# Power.net
KiCad netlist of a schematic drawn in Altium Designer
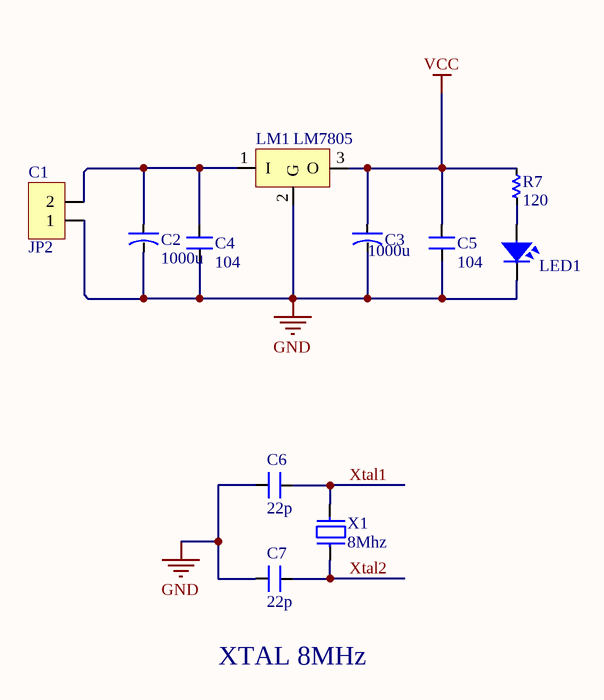
[diagram p0: Power.SchDoc]

(export (version "E")
  (design (tool "Eeschema 10.0.6"))
  (components
    (comp (ref "C1")
      (value "JP2")
      (footprint "JP2-D1T")
      (description "WR-PHD 2.54 mm Angled Socket Header")
      (fields
        (field (name "MANUFACTURER") "Würth Elektronik eiSos GmbH")
        (field (name "PARTNO") "613002143121")
        (field (name "CREATED BY") "Karrer Zheng")
      )
      (libsource (lib "LIBRARY") (part "JP2"))
    )
    (comp (ref "C2")
      (value "1000u")
      (footprint "CA-ALU-2.54")
      (description "Capacitor (Semiconductor SIM Model)")
      (fields (field (name "PUBLISHER") "Altium Limited"))
      (libsource (lib "LIBRARY") (part "CN-ALU-DIP"))
    )
    (comp (ref "C3")
      (value "1000u")
      (footprint "CA-ALU-2.54")
      (description "Capacitor (Semiconductor SIM Model)")
      (fields (field (name "PUBLISHER") "Altium Limited"))
      (libsource (lib "LIBRARY") (part "CN-ALU-DIP"))
    )
    (comp (ref "C4")
      (value "104")
      (footprint "C-SE-7,5x11x13x9x4")
      (description "Capacitor (Semiconductor SIM Model)")
      (fields (field (name "PUBLISHER") "Altium Limited"))
      (libsource (lib "LIBRARY") (part "CN-SEMI-DIP"))
    )
    (comp (ref "C5")
      (value "104")
      (footprint "C-SE-7,5x11x13x9x4")
      (description "Capacitor (Semiconductor SIM Model)")
      (fields (field (name "PUBLISHER") "Altium Limited"))
      (libsource (lib "LIBRARY") (part "CN-SEMI-DIP"))
    )
    (comp (ref "C6")
      (value "22p")
      (footprint "C-SE-7,5x11x13x9x4")
      (description "Capacitor (Semiconductor SIM Model)")
      (fields (field (name "PUBLISHER") "Altium Limited"))
      (libsource (lib "LIBRARY") (part "CN-SEMI-DIP"))
    )
    (comp (ref "C7")
      (value "22p")
      (footprint "C-SE-7,5x11x13x9x4")
      (description "Capacitor (Semiconductor SIM Model)")
      (fields (field (name "PUBLISHER") "Altium Limited"))
      (libsource (lib "LIBRARY") (part "CN-SEMI-DIP"))
    )
    (comp (ref "LED1")
      (value "LED")
      (footprint "LED-3MM-RED")
      (description "LED Single colour Green and Red")
      (libsource (lib "LIBRARY") (part "LED"))
    )
    (comp (ref "LM1")
      (value "LM78xx")
      (footprint "TO92-321")
      (description "Positive Voltage Regulator")
      (fields (field (name "PUBLISHER") "Altium Limited"))
      (libsource (lib "LIBRARY") (part "LM78xx"))
    )
    (comp (ref "R7")
      (value "120")
      (footprint "RES-1/2W")
      (description "Res")
      (fields
        (field (name "MANUFACTURER") "Generic Components")
        (field (name "PUBLISHER") "Altium Hobart Technology Centre")
      )
      (libsource (lib "LIBRARY") (part "Res"))
    )
    (comp (ref "X1")
      (value "8Mhz")
      (footprint "XT2")
      (description "Crystal, 32.768 KHz, -40 to 85 degC, 3.2 x 1.5 x 0.9 mm SMD")
      (libsource (lib "LIBRARY") (part "XT2"))
    )
  )
  (nets
    (net (code "1") (name "/Xtal1") (class "Default")
      (node (ref "C6") (pin "2") (pinfunction "2_2") (pintype "passive"))
      (node (ref "X1") (pin "2") (pinfunction "2_2") (pintype "passive"))
    )
    (net (code "2") (name "/Xtal2") (class "Default")
      (node (ref "C7") (pin "2") (pinfunction "2_2") (pintype "passive"))
      (node (ref "X1") (pin "1") (pinfunction "1_1") (pintype "passive"))
    )
    (net (code "3") (name "GND") (class "Default")
      (node (ref "C1") (pin "1") (pinfunction "1_1") (pintype "passive"))
      (node (ref "C2") (pin "2") (pinfunction "2_2") (pintype "passive"))
      (node (ref "C3") (pin "2") (pinfunction "2_2") (pintype "passive"))
      (node (ref "C4") (pin "1") (pinfunction "1_1") (pintype "passive"))
      (node (ref "C5") (pin "1") (pinfunction "1_1") (pintype "passive"))
      (node (ref "C6") (pin "1") (pinfunction "1_1") (pintype "passive"))
      (node (ref "C7") (pin "1") (pinfunction "1_1") (pintype "passive"))
      (node (ref "LED1") (pin "2") (pinfunction "2_2") (pintype "passive"))
      (node (ref "LM1") (pin "2") (pinfunction "G_2") (pintype "power_in"))
    )
    (net (code "4") (name "Net-(LED1-Pad1)") (class "Default")
      (node (ref "LED1") (pin "1") (pinfunction "1_1") (pintype "passive"))
      (node (ref "R7") (pin "2") (pinfunction "2_2") (pintype "passive"))
    )
    (net (code "5") (name "Net-(LM1-I)") (class "Default")
      (node (ref "C1") (pin "2") (pinfunction "2_2") (pintype "passive"))
      (node (ref "C2") (pin "1") (pinfunction "1_1") (pintype "passive"))
      (node (ref "C4") (pin "2") (pinfunction "2_2") (pintype "passive"))
      (node (ref "LM1") (pin "1") (pinfunction "I_1") (pintype "power_in"))
    )
    (net (code "6") (name "VCC") (class "Default")
      (node (ref "C3") (pin "1") (pinfunction "1_1") (pintype "passive"))
      (node (ref "C5") (pin "2") (pinfunction "2_2") (pintype "passive"))
      (node (ref "LM1") (pin "3") (pinfunction "O_3") (pintype "power_in"))
      (node (ref "R7") (pin "1") (pinfunction "1_1") (pintype "passive"))
    )
  )
)
